# devaamo_myhalf.net
KiCad netlist of a schematic drawn in EAGLE
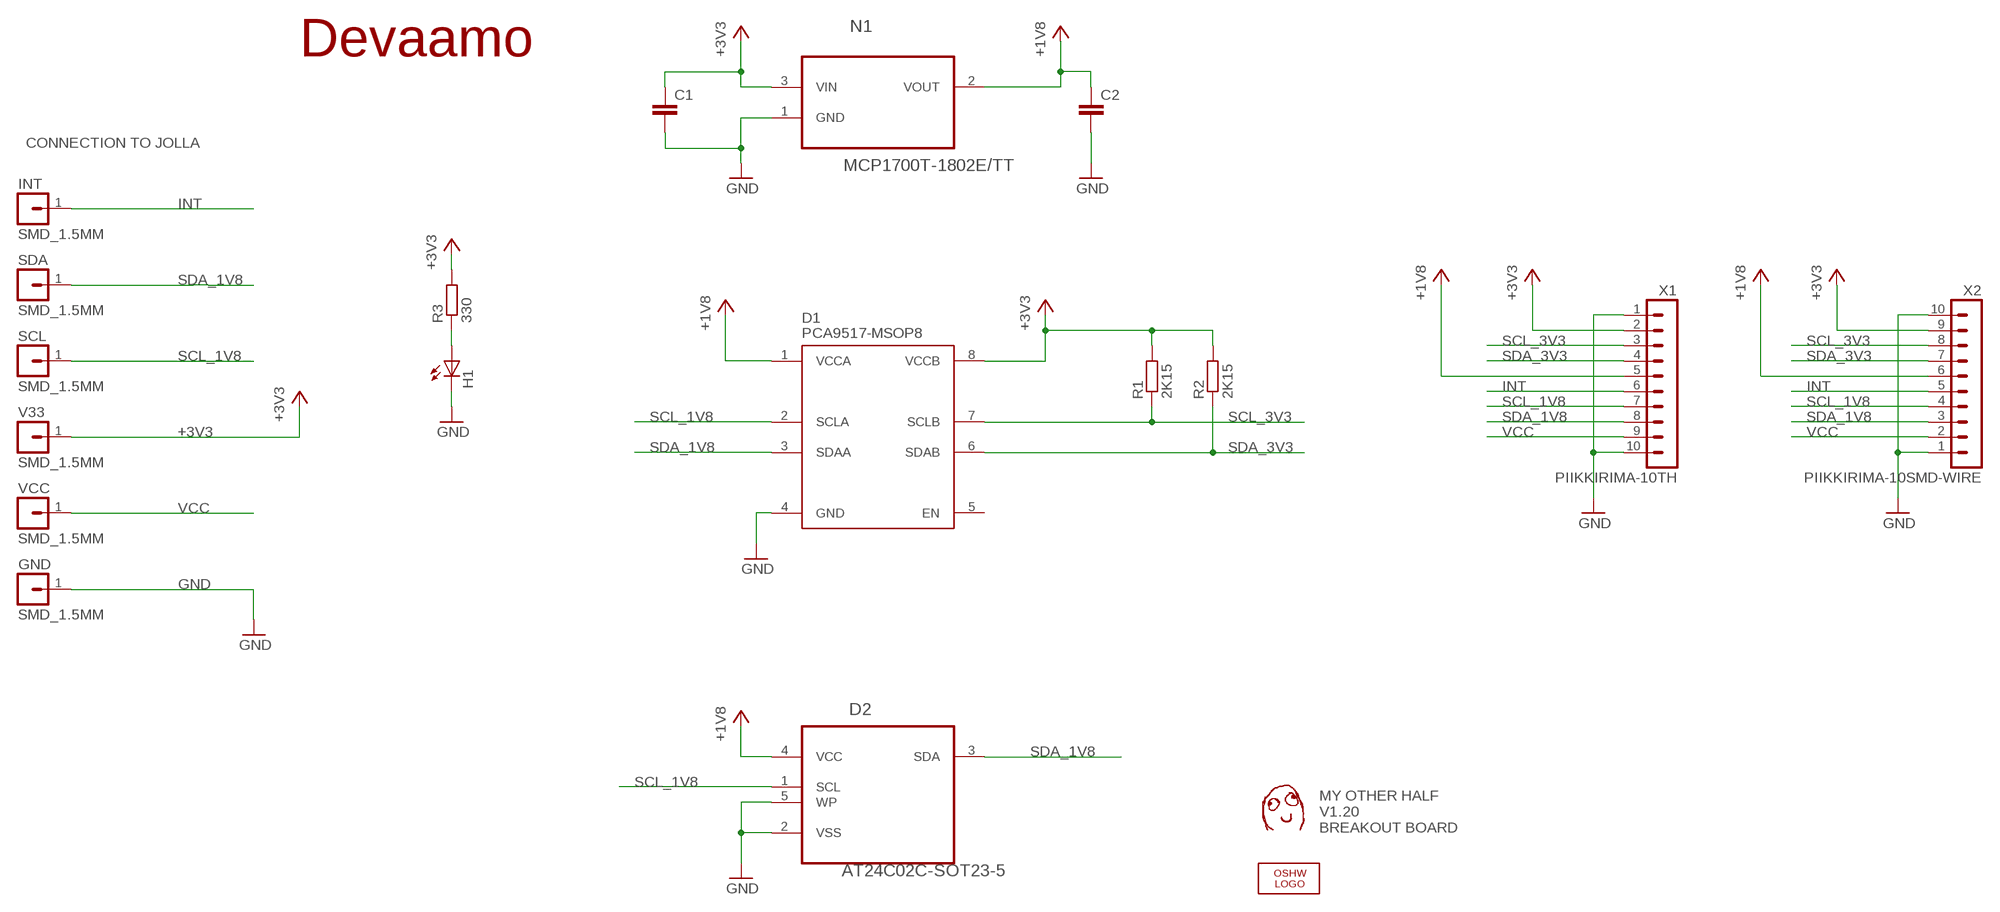
[diagram p0: schematic, sheet 1]

(export (version "E")
  (design (tool "Eeschema 10.0.6"))
  (components
    (comp (ref "C1")
      (value "C-EUC0603")
      (footprint "eagle-import:C0603")
      (libsource (lib "eagle-import") (part "C-EUC0603"))
    )
    (comp (ref "C2")
      (value "C-EUC0603")
      (footprint "eagle-import:C0603")
      (libsource (lib "eagle-import") (part "C-EUC0603"))
    )
    (comp (ref "D1")
      (value "PCA9517-MSOP8")
      (footprint "eagle-import:SOP65P490X110-8N")
      (libsource (lib "eagle-import") (part "PCA9517"))
    )
    (comp (ref "D2")
      (value "AT24C02C-SOT23-5")
      (footprint "eagle-import:SOT95P280X145-5N")
      (fields (field (name "MPN") "24LC01BT-I/OT"))
      (libsource (lib "eagle-import") (part "24LC01BT-I/OT"))
    )
    (comp (ref "GND")
      (value "SMD_1.5MM")
      (footprint "eagle-import:SMD_ROUND_1.5MM")
      (libsource (lib "eagle-import") (part "SMD_1.5MM"))
    )
    (comp (ref "H1")
      (value "LEDCHIP-LED0603")
      (footprint "eagle-import:CHIP-LED0603")
      (libsource (lib "eagle-import") (part "LEDCHIP-LED0603"))
    )
    (comp (ref "INT")
      (value "SMD_1.5MM")
      (footprint "eagle-import:SMD_ROUND_1.5MM")
      (libsource (lib "eagle-import") (part "SMD_1.5MM"))
    )
    (comp (ref "LOGO1")
      (value "OSHW_LOGO_FILLX0200-NT")
      (footprint "eagle-import:OSHW_FILLX200_NOTEXT")
      (libsource (lib "eagle-import") (part "OSHW_LOGO_FILLX0200-NT"))
    )
    (comp (ref "N1")
      (value "MCP1700T-1802E/TT")
      (footprint "eagle-import:SOT95P237X112-3N")
      (libsource (lib "eagle-import") (part "MCP1700T-1802E/TT"))
    )
    (comp (ref "R1")
      (value "2K15")
      (footprint "eagle-import:R0603")
      (libsource (lib "eagle-import") (part "R-EU_R0603"))
    )
    (comp (ref "R2")
      (value "2K15")
      (footprint "eagle-import:R0603")
      (libsource (lib "eagle-import") (part "R-EU_R0603"))
    )
    (comp (ref "R3")
      (value "330")
      (footprint "eagle-import:R0603")
      (libsource (lib "eagle-import") (part "R-EU_R0603"))
    )
    (comp (ref "SCL")
      (value "SMD_1.5MM")
      (footprint "eagle-import:SMD_ROUND_1.5MM")
      (libsource (lib "eagle-import") (part "SMD_1.5MM"))
    )
    (comp (ref "SDA")
      (value "SMD_1.5MM")
      (footprint "eagle-import:SMD_ROUND_1.5MM")
      (libsource (lib "eagle-import") (part "SMD_1.5MM"))
    )
    (comp (ref "U$1")
      (value "DAFUG")
      (footprint "eagle-import:DAFUG")
      (libsource (lib "eagle-import") (part "DAFUG"))
    )
    (comp (ref "U$3")
      (value "DEVAAMO")
      (footprint "eagle-import:DEVAAMO")
      (libsource (lib "eagle-import") (part "DEVAAMO"))
    )
    (comp (ref "V33")
      (value "SMD_1.5MM")
      (footprint "eagle-import:SMD_ROUND_1.5MM")
      (libsource (lib "eagle-import") (part "SMD_1.5MM"))
    )
    (comp (ref "VCC")
      (value "SMD_1.5MM")
      (footprint "eagle-import:SMD_ROUND_1.5MM")
      (libsource (lib "eagle-import") (part "SMD_1.5MM"))
    )
    (comp (ref "X1")
      (value "PIIKKIRIMA-10TH")
      (footprint "eagle-import:PIIKKIRIMA-10")
      (libsource (lib "eagle-import") (part "PIIKKIRIMA-10TH"))
    )
    (comp (ref "X2")
      (value "PIIKKIRIMA-10SMD-WIRE")
      (footprint "eagle-import:61001018321")
      (libsource (lib "eagle-import") (part "PIIKKIRIMA-10SMD-WIRE"))
    )
  )
  (nets
    (net (code "1") (name "+1V8") (class "Default")
      (node (ref "C2") (pin "1") (pinfunction "1_1") (pintype "passive"))
      (node (ref "D1") (pin "1") (pinfunction "VCCA_1") (pintype "bidirectional"))
      (node (ref "D2") (pin "4") (pinfunction "VCC_4") (pintype "power_in"))
      (node (ref "N1") (pin "2") (pinfunction "VOUT_2") (pintype "output"))
      (node (ref "X1") (pin "5") (pinfunction "5_5") (pintype "passive"))
      (node (ref "X2") (pin "6") (pinfunction "5_6") (pintype "passive"))
    )
    (net (code "2") (name "+3V3") (class "Default")
      (node (ref "C1") (pin "1") (pinfunction "1_1") (pintype "passive"))
      (node (ref "D1") (pin "8") (pinfunction "VCCB_8") (pintype "bidirectional"))
      (node (ref "N1") (pin "3") (pinfunction "VIN_3") (pintype "input"))
      (node (ref "R1") (pin "2") (pinfunction "2_2") (pintype "passive"))
      (node (ref "R2") (pin "2") (pinfunction "2_2") (pintype "passive"))
      (node (ref "R3") (pin "2") (pinfunction "2_2") (pintype "passive"))
      (node (ref "V33") (pin "1") (pinfunction "1_1") (pintype "passive"))
      (node (ref "X1") (pin "2") (pinfunction "2_2") (pintype "passive"))
      (node (ref "X2") (pin "9") (pinfunction "2_9") (pintype "passive"))
    )
    (net (code "3") (name "/INT") (class "Default")
      (node (ref "INT") (pin "1") (pinfunction "1_1") (pintype "passive"))
      (node (ref "X1") (pin "6") (pinfunction "6_6") (pintype "passive"))
      (node (ref "X2") (pin "5") (pinfunction "6_5") (pintype "passive"))
    )
    (net (code "4") (name "/SCL_1V8") (class "Default")
      (node (ref "D1") (pin "2") (pinfunction "SCLA_2") (pintype "bidirectional"))
      (node (ref "D2") (pin "1") (pinfunction "SCL_1") (pintype "input"))
      (node (ref "SCL") (pin "1") (pinfunction "1_1") (pintype "passive"))
      (node (ref "X1") (pin "7") (pinfunction "7_7") (pintype "passive"))
      (node (ref "X2") (pin "4") (pinfunction "7_4") (pintype "passive"))
    )
    (net (code "5") (name "/SCL_3V3") (class "Default")
      (node (ref "D1") (pin "7") (pinfunction "SCLB_7") (pintype "bidirectional"))
      (node (ref "R1") (pin "1") (pinfunction "1_1") (pintype "passive"))
      (node (ref "X1") (pin "3") (pinfunction "3_3") (pintype "passive"))
      (node (ref "X2") (pin "8") (pinfunction "3_8") (pintype "passive"))
    )
    (net (code "6") (name "/SDA_1V8") (class "Default")
      (node (ref "D1") (pin "3") (pinfunction "SDAA_3") (pintype "bidirectional"))
      (node (ref "D2") (pin "3") (pinfunction "SDA_3") (pintype "bidirectional"))
      (node (ref "SDA") (pin "1") (pinfunction "1_1") (pintype "passive"))
      (node (ref "X1") (pin "8") (pinfunction "8_8") (pintype "passive"))
      (node (ref "X2") (pin "3") (pinfunction "8_3") (pintype "passive"))
    )
    (net (code "7") (name "/SDA_3V3") (class "Default")
      (node (ref "D1") (pin "6") (pinfunction "SDAB_6") (pintype "bidirectional"))
      (node (ref "R2") (pin "1") (pinfunction "1_1") (pintype "passive"))
      (node (ref "X1") (pin "4") (pinfunction "4_4") (pintype "passive"))
      (node (ref "X2") (pin "7") (pinfunction "4_7") (pintype "passive"))
    )
    (net (code "8") (name "/VCC") (class "Default")
      (node (ref "VCC") (pin "1") (pinfunction "1_1") (pintype "passive"))
      (node (ref "X1") (pin "9") (pinfunction "9_9") (pintype "passive"))
      (node (ref "X2") (pin "2") (pinfunction "9_2") (pintype "passive"))
    )
    (net (code "9") (name "GND") (class "Default")
      (node (ref "C1") (pin "2") (pinfunction "2_2") (pintype "passive"))
      (node (ref "C2") (pin "2") (pinfunction "2_2") (pintype "passive"))
      (node (ref "D1") (pin "4") (pinfunction "GND_4") (pintype "bidirectional"))
      (node (ref "D2") (pin "2") (pinfunction "VSS_2") (pintype "passive"))
      (node (ref "D2") (pin "5") (pinfunction "WP_5") (pintype "input"))
      (node (ref "GND") (pin "1") (pinfunction "1_1") (pintype "passive"))
      (node (ref "H1") (pin "C") (pinfunction "C_C") (pintype "passive"))
      (node (ref "N1") (pin "1") (pinfunction "GND_1") (pintype "passive"))
      (node (ref "X1") (pin "1") (pinfunction "1_1") (pintype "passive"))
      (node (ref "X1") (pin "10") (pinfunction "10_10") (pintype "passive"))
      (node (ref "X2") (pin "1") (pinfunction "10_1") (pintype "passive"))
      (node (ref "X2") (pin "10") (pinfunction "1_10") (pintype "passive"))
    )
    (net (code "10") (name "Net-(H1-PadA)") (class "Default")
      (node (ref "H1") (pin "A") (pinfunction "A_A") (pintype "passive"))
      (node (ref "R3") (pin "1") (pinfunction "1_1") (pintype "passive"))
    )
    (net (code "11") (name "unconnected-(D1-EN-Pad5)") (class "Default")
      (node (ref "D1") (pin "5") (pinfunction "EN_5") (pintype "bidirectional"))
    )
  )
)
